# WL_RFFC.net
KiCad netlist of a schematic drawn in Altium Designer
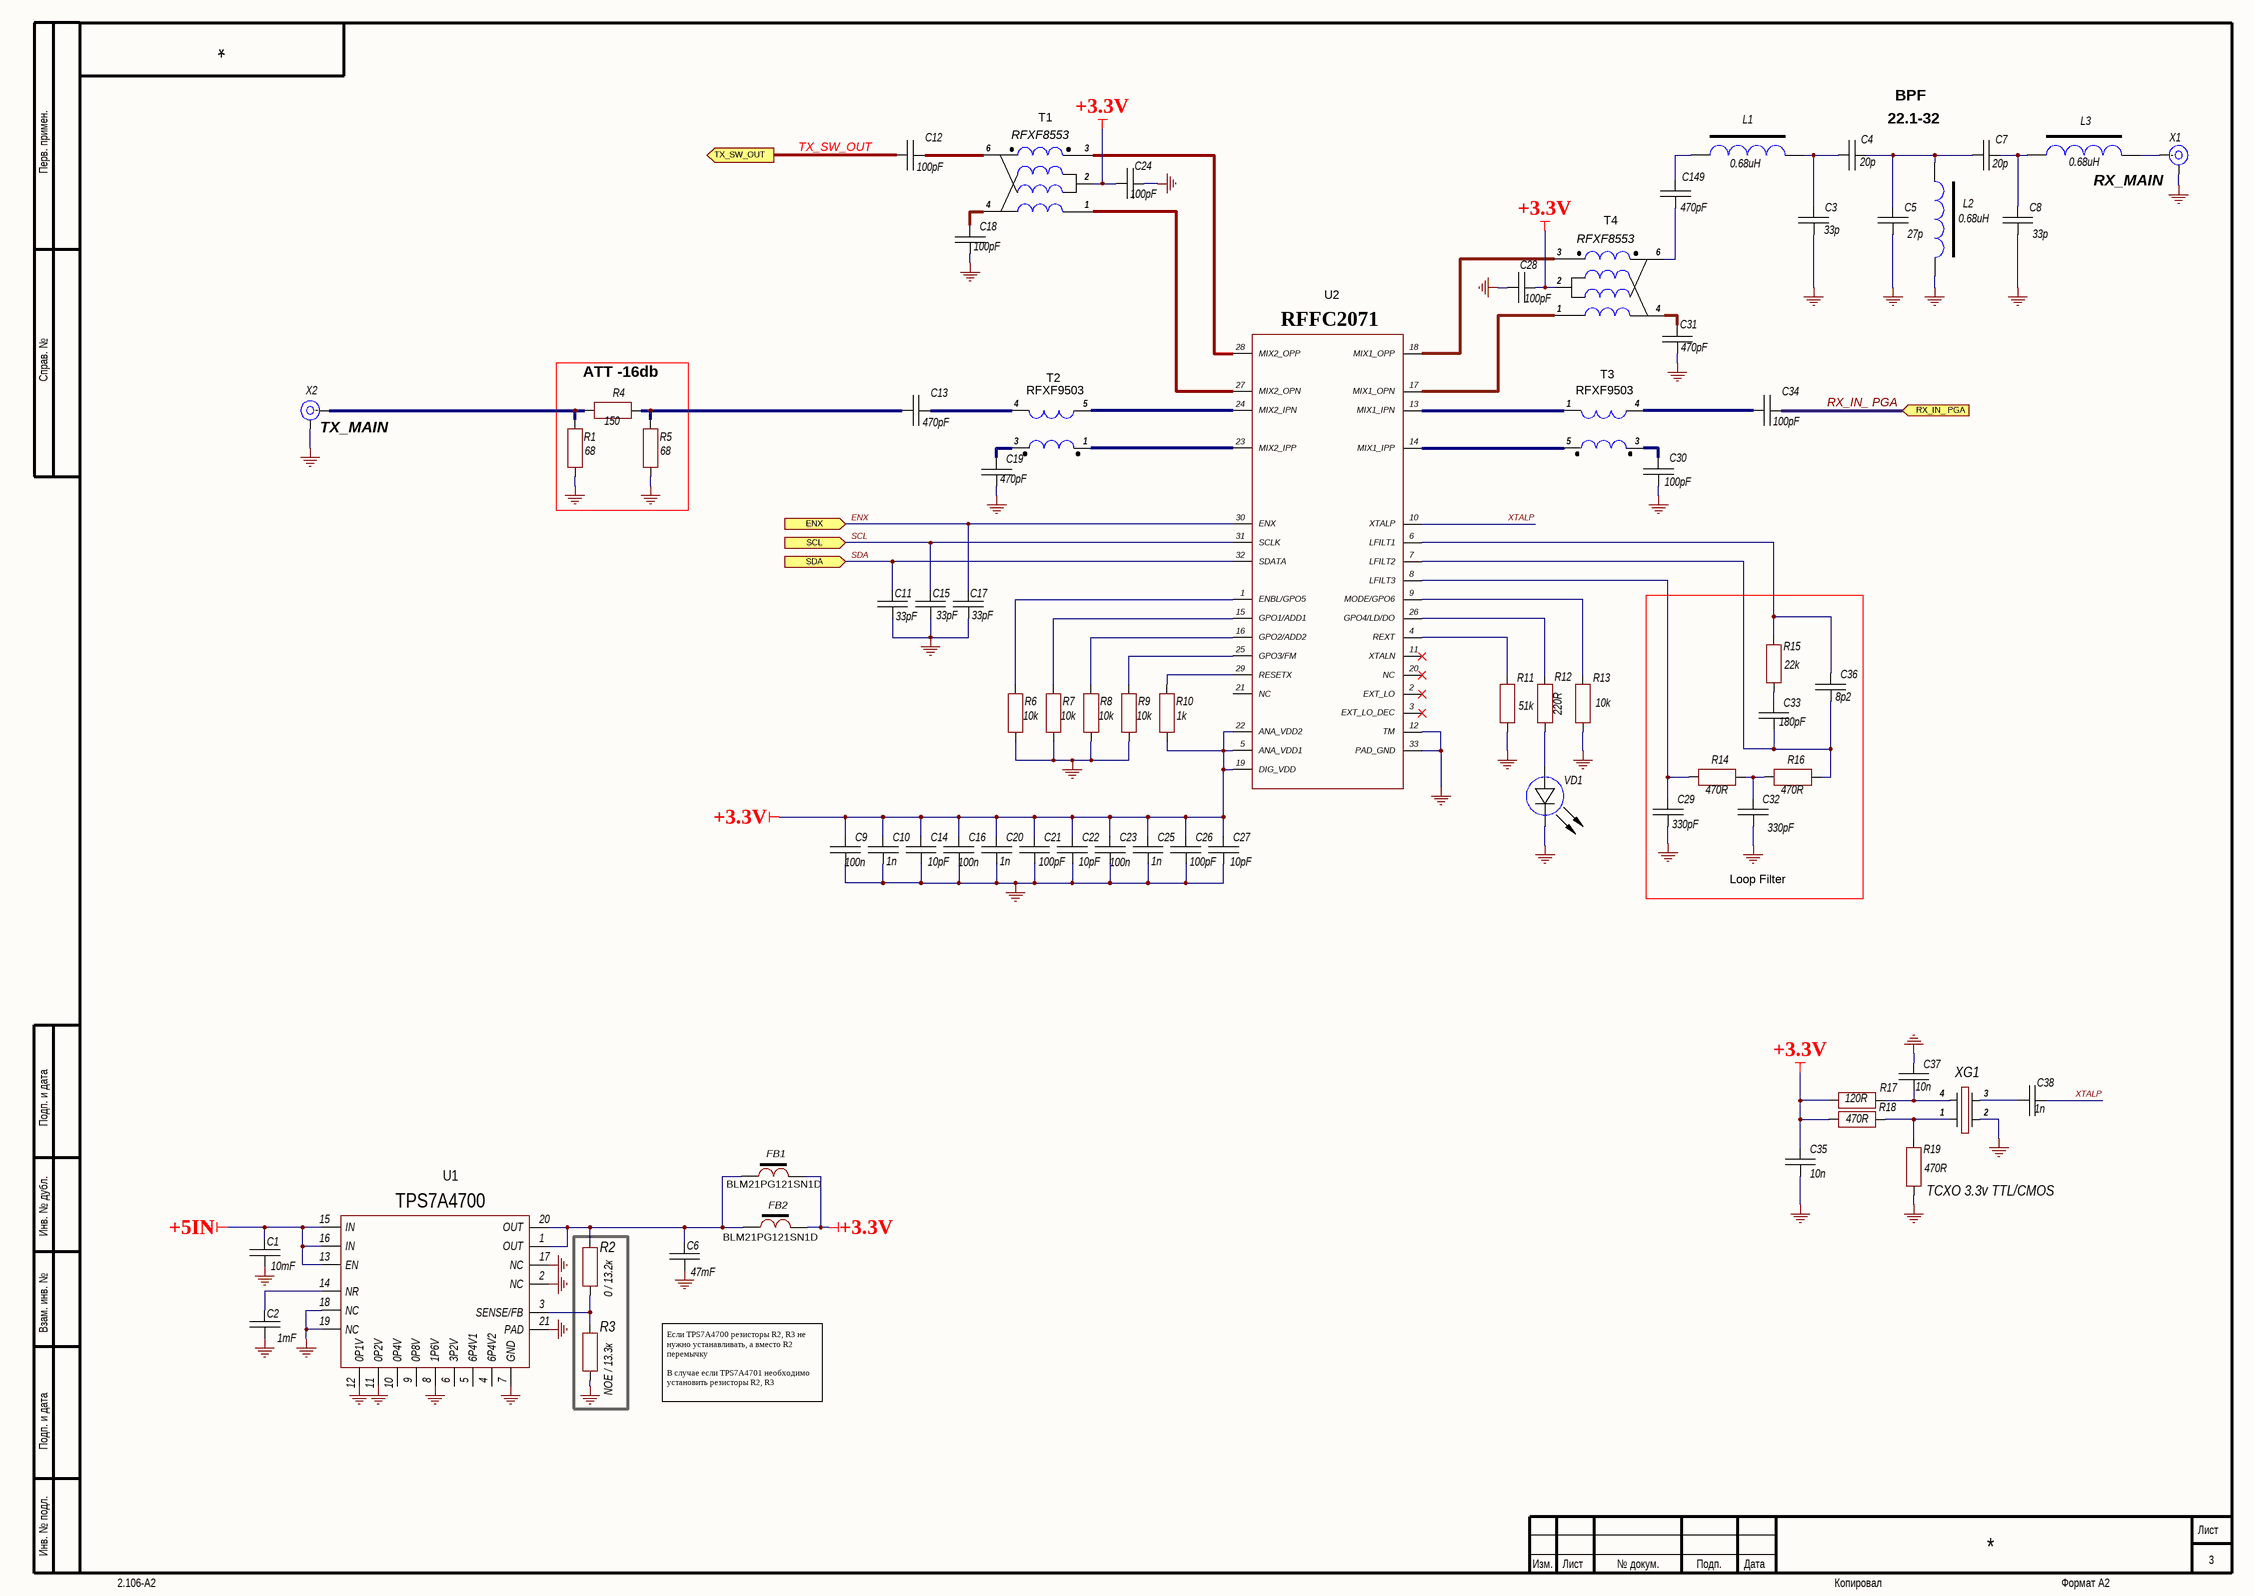
[diagram p0: WL_RFFC.SchDoc]

(export (version "E")
  (design (tool "Eeschema 10.0.6"))
  (components
    (comp (ref "C1")
      (value "10mF")
      (footprint "standard:CH1206C")
      (libsource (lib "Discrete") (part "Capacitor"))
    )
    (comp (ref "C2")
      (value "1mF")
      (footprint "standard:CH0805C")
      (libsource (lib "Discrete") (part "Capacitor"))
    )
    (comp (ref "C3")
      (value "33p")
      (footprint "standard:CH0805C")
      (libsource (lib "Discrete") (part "Capacitor"))
    )
    (comp (ref "C4")
      (value "20p")
      (footprint "standard:CH0805C")
      (libsource (lib "Discrete") (part "Capacitor"))
    )
    (comp (ref "C5")
      (value "27p")
      (footprint "standard:CH0805C")
      (libsource (lib "Discrete") (part "Capacitor"))
    )
    (comp (ref "C6")
      (value "47mF")
      (footprint "standard:CH1206C")
      (libsource (lib "Discrete") (part "Capacitor"))
    )
    (comp (ref "C7")
      (value "20p")
      (footprint "standard:CH0805C")
      (libsource (lib "Discrete") (part "Capacitor"))
    )
    (comp (ref "C8")
      (value "33p")
      (footprint "standard:CH0805C")
      (libsource (lib "Discrete") (part "Capacitor"))
    )
    (comp (ref "C9")
      (value "100n")
      (footprint "standard:CH0805C")
      (libsource (lib "Discrete") (part "Capacitor"))
    )
    (comp (ref "C10")
      (value "1n")
      (footprint "standard:CH0805C")
      (libsource (lib "Discrete") (part "Capacitor"))
    )
    (comp (ref "C11")
      (value "33pF")
      (footprint "standard:CH0805C")
      (libsource (lib "Discrete") (part "Capacitor"))
    )
    (comp (ref "C12")
      (value "100pF")
      (footprint "standard:CH0805C")
      (libsource (lib "Discrete") (part "Capacitor"))
    )
    (comp (ref "C13")
      (value "470pF")
      (footprint "standard:CH0805C")
      (libsource (lib "Discrete") (part "Capacitor"))
    )
    (comp (ref "C14")
      (value "10pF")
      (footprint "standard:CH0805C")
      (libsource (lib "Discrete") (part "Capacitor"))
    )
    (comp (ref "C15")
      (value "33pF")
      (footprint "standard:CH0805C")
      (libsource (lib "Discrete") (part "Capacitor"))
    )
    (comp (ref "C16")
      (value "100n")
      (footprint "standard:CH0805C")
      (libsource (lib "Discrete") (part "Capacitor"))
    )
    (comp (ref "C17")
      (value "33pF")
      (footprint "standard:CH0805C")
      (libsource (lib "Discrete") (part "Capacitor"))
    )
    (comp (ref "C18")
      (value "100pF")
      (footprint "standard:CH0805C")
      (libsource (lib "Discrete") (part "Capacitor"))
    )
    (comp (ref "C19")
      (value "470pF")
      (footprint "standard:CH0805C")
      (libsource (lib "Discrete") (part "Capacitor"))
    )
    (comp (ref "C20")
      (value "1n")
      (footprint "standard:CH0805C")
      (libsource (lib "Discrete") (part "Capacitor"))
    )
    (comp (ref "C21")
      (value "100pF")
      (footprint "standard:CH0805C")
      (libsource (lib "Discrete") (part "Capacitor"))
    )
    (comp (ref "C22")
      (value "10pF")
      (footprint "standard:CH0805C")
      (libsource (lib "Discrete") (part "Capacitor"))
    )
    (comp (ref "C23")
      (value "100n")
      (footprint "standard:CH0805C")
      (libsource (lib "Discrete") (part "Capacitor"))
    )
    (comp (ref "C24")
      (value "100pF")
      (footprint "standard:CH0805C")
      (libsource (lib "Discrete") (part "Capacitor"))
    )
    (comp (ref "C25")
      (value "1n")
      (footprint "standard:CH0805C")
      (libsource (lib "Discrete") (part "Capacitor"))
    )
    (comp (ref "C26")
      (value "100pF")
      (footprint "standard:CH0805C")
      (libsource (lib "Discrete") (part "Capacitor"))
    )
    (comp (ref "C27")
      (value "10pF")
      (footprint "standard:CH0805C")
      (libsource (lib "Discrete") (part "Capacitor"))
    )
    (comp (ref "C28")
      (value "100pF")
      (footprint "standard:CH0805C")
      (libsource (lib "Discrete") (part "Capacitor"))
    )
    (comp (ref "C29")
      (value "330pF")
      (footprint "standard:CH0805C")
      (libsource (lib "Discrete") (part "Capacitor"))
    )
    (comp (ref "C30")
      (value "100pF")
      (footprint "standard:CH0805C")
      (libsource (lib "Discrete") (part "Capacitor"))
    )
    (comp (ref "C31")
      (value "470pF")
      (footprint "standard:CH0805C")
      (libsource (lib "Discrete") (part "Capacitor"))
    )
    (comp (ref "C32")
      (value "330pF")
      (footprint "standard:CH0805C")
      (libsource (lib "Discrete") (part "Capacitor"))
    )
    (comp (ref "C33")
      (value "180pF")
      (footprint "standard:CH0805C")
      (libsource (lib "Discrete") (part "Capacitor"))
    )
    (comp (ref "C34")
      (value "100pF")
      (footprint "standard:CH0805C")
      (libsource (lib "Discrete") (part "Capacitor"))
    )
    (comp (ref "C35")
      (value "10n")
      (footprint "standard:CH0805C")
      (libsource (lib "Discrete") (part "Capacitor"))
    )
    (comp (ref "C36")
      (value "8p2")
      (footprint "standard:CH0805C")
      (libsource (lib "Discrete") (part "Capacitor"))
    )
    (comp (ref "C37")
      (value "10n")
      (footprint "standard:CH0805C")
      (libsource (lib "Discrete") (part "Capacitor"))
    )
    (comp (ref "C38")
      (value "1n")
      (footprint "standard:CH0805C")
      (libsource (lib "Discrete") (part "Capacitor"))
    )
    (comp (ref "C149")
      (value "470pF")
      (footprint "standard:CH0805C")
      (libsource (lib "Discrete") (part "Capacitor"))
    )
    (comp (ref "FB1")
      (value "BLM21PG121SN1D")
      (footprint "CH0805L")
      (libsource (lib "Discrete") (part "FB-1"))
    )
    (comp (ref "FB2")
      (value "BLM21PG121SN1D")
      (footprint "CH0805L")
      (libsource (lib "Discrete") (part "FB-1"))
    )
    (comp (ref "L1") (value "0.68uH") (footprint "L1210") (libsource (lib "") (part "TRANS_1")))
    (comp (ref "L2") (value "0.68uH") (footprint "L1210") (libsource (lib "Transformers") (part "TRANS")))
    (comp (ref "L3") (value "0.68uH") (footprint "L1210") (libsource (lib "") (part "TRANS_1")))
    (comp (ref "R1") (value "68") (footprint "standard:CH1206R") (libsource (lib "") (part "Resistor_1")))
    (comp (ref "R2")
      (value "0 / 13.2к")
      (footprint "standard:CH0805R")
      (libsource (lib "Discrete") (part "Resistor"))
    )
    (comp (ref "R3")
      (value "NOE / 13.3к")
      (footprint "standard:CH0805R")
      (libsource (lib "Discrete") (part "Resistor"))
    )
    (comp (ref "R4") (value "150") (footprint "standard:CH1206R") (libsource (lib "") (part "Resistor_2")))
    (comp (ref "R5") (value "68") (footprint "standard:CH1206R") (libsource (lib "") (part "Resistor_1")))
    (comp (ref "R6") (value "10k") (footprint "standard:CH0805R") (libsource (lib "") (part "Resistor_1")))
    (comp (ref "R7") (value "10k") (footprint "standard:CH0805R") (libsource (lib "") (part "Resistor_1")))
    (comp (ref "R8") (value "10k") (footprint "standard:CH0805R") (libsource (lib "") (part "Resistor_1")))
    (comp (ref "R9") (value "10k") (footprint "standard:CH0805R") (libsource (lib "") (part "Resistor_1")))
    (comp (ref "R10") (value "1k") (footprint "standard:CH0805R") (libsource (lib "") (part "Resistor_1")))
    (comp (ref "R11") (value "51k") (footprint "standard:CH0805R") (libsource (lib "") (part "Resistor_1")))
    (comp (ref "R12") (value "220R") (footprint "standard:CH0805R") (libsource (lib "") (part "Resistor_1")))
    (comp (ref "R13") (value "10k") (footprint "standard:CH0805R") (libsource (lib "") (part "Resistor_1")))
    (comp (ref "R14") (value "470R") (footprint "standard:CH0805R") (libsource (lib "") (part "Resistor_2")))
    (comp (ref "R15")
      (value "22k")
      (footprint "standard:CH0805R")
      (libsource (lib "Discrete") (part "Resistor"))
    )
    (comp (ref "R16") (value "470R") (footprint "standard:CH0805R") (libsource (lib "") (part "Resistor_2")))
    (comp (ref "R17") (value "120R") (footprint "standard:CH0805R") (libsource (lib "") (part "Resistor_2")))
    (comp (ref "R18") (value "470R") (footprint "standard:CH0805R") (libsource (lib "") (part "Resistor_2")))
    (comp (ref "R19")
      (value "470R")
      (footprint "standard:CH0805R")
      (libsource (lib "Discrete") (part "Resistor"))
    )
    (comp (ref "T1") (value "RFXF8553") (footprint "TC4-1-ADT4-6") (libsource (lib "") (part "RFXF8553_1")))
    (comp (ref "T2")
      (value "RFXF9503")
      (footprint "TC4-1/RFXF8553")
      (libsource (lib "Transformers") (part "RFXF9503"))
    )
    (comp (ref "T3") (value "RFXF9503") (footprint "TC4-1/RFXF8553") (libsource (lib "") (part "RFXF9503_1")))
    (comp (ref "T4")
      (value "RFXF8553")
      (footprint "TC4-1-ADT4-6")
      (libsource (lib "Transformers") (part "RFXF8553"))
    )
    (comp (ref "U1")
      (value "TPS7A4700")
      (footprint "20-VQFN (5x5 mm)")
      (libsource (lib "Power Supplies") (part "TPS7A4700"))
    )
    (comp (ref "U2")
      (value "RFFC2071")
      (footprint "32-VQFN (5x5 mm)")
      (libsource (lib "Digital") (part "RFFC2071"))
    )
    (comp (ref "VD1") (value "*") (footprint "standard:CH0805LB") (libsource (lib "Discrete") (part "LED")))
    (comp (ref "X1")
      (value "RX_MAIN")
      (footprint "custom:CON: SMA")
      (description "RF")
      (libsource (lib "Connectors") (part "SMA"))
    )
    (comp (ref "X2")
      (value "TX_MAIN")
      (footprint "custom:CON: SMA")
      (description "RF")
      (libsource (lib "Connectors") (part "SMA"))
    )
    (comp (ref "XG1")
      (value "TCXO 3.3v TTL/CMOS")
      (footprint "TCXO")
      (libsource (lib "Discrete") (part "Generator"))
    )
  )
  (nets
    (net (code "1") (name "+3.3V") (class "Default")
      (node (ref "C10") (pin "2") (pinfunction "2_2") (pintype "power_in"))
      (node (ref "C14") (pin "2") (pinfunction "2_2") (pintype "power_in"))
      (node (ref "C16") (pin "2") (pinfunction "2_2") (pintype "power_in"))
      (node (ref "C20") (pin "2") (pinfunction "2_2") (pintype "power_in"))
      (node (ref "C21") (pin "2") (pinfunction "2_2") (pintype "power_in"))
      (node (ref "C22") (pin "2") (pinfunction "2_2") (pintype "power_in"))
      (node (ref "C23") (pin "2") (pinfunction "2_2") (pintype "power_in"))
      (node (ref "C24") (pin "2") (pinfunction "2_2") (pintype "power_in"))
      (node (ref "C25") (pin "2") (pinfunction "2_2") (pintype "power_in"))
      (node (ref "C26") (pin "2") (pinfunction "2_2") (pintype "power_in"))
      (node (ref "C27") (pin "2") (pinfunction "2_2") (pintype "power_in"))
      (node (ref "C28") (pin "2") (pinfunction "2_2") (pintype "power_in"))
      (node (ref "C35") (pin "2") (pinfunction "2_2") (pintype "power_in"))
      (node (ref "C9") (pin "2") (pinfunction "2_2") (pintype "power_in"))
      (node (ref "FB1") (pin "2") (pinfunction "2_2") (pintype "passive"))
      (node (ref "FB2") (pin "2") (pinfunction "2_2") (pintype "passive"))
      (node (ref "R10") (pin "2") (pinfunction "2_2") (pintype "passive"))
      (node (ref "R17") (pin "1") (pinfunction "1_1") (pintype "passive"))
      (node (ref "R18") (pin "1") (pinfunction "1_1") (pintype "passive"))
      (node (ref "T1") (pin "2") (pinfunction "2_2") (pintype "passive"))
      (node (ref "T4") (pin "2") (pinfunction "2_2") (pintype "passive"))
      (node (ref "U2") (pin "19") (pinfunction "DIG_VDD_19") (pintype "passive"))
      (node (ref "U2") (pin "22") (pinfunction "ANA_VDD2_22") (pintype "passive"))
      (node (ref "U2") (pin "5") (pinfunction "ANA_VDD1_5") (pintype "passive"))
    )
    (net (code "2") (name "+5IN") (class "Default")
      (node (ref "C1") (pin "2") (pinfunction "2_2") (pintype "power_in"))
      (node (ref "U1") (pin "13") (pinfunction "EN_13") (pintype "power_in"))
      (node (ref "U1") (pin "15") (pinfunction "IN_15") (pintype "power_in"))
      (node (ref "U1") (pin "16") (pinfunction "IN_16") (pintype "power_in"))
    )
    (net (code "3") (name "/ENX") (class "Default")
      (node (ref "C17") (pin "2") (pinfunction "2_2") (pintype "power_in"))
      (node (ref "U2") (pin "30") (pinfunction "ENX_30") (pintype "passive"))
    )
    (net (code "4") (name "/RX_IN_ PGA") (class "Default")
      (node (ref "C34") (pin "1") (pinfunction "1_1") (pintype "power_in"))
    )
    (net (code "5") (name "/SCL") (class "Default")
      (node (ref "C15") (pin "2") (pinfunction "2_2") (pintype "power_in"))
      (node (ref "U2") (pin "31") (pinfunction "SCLK_31") (pintype "passive"))
    )
    (net (code "6") (name "/SDA") (class "Default")
      (node (ref "C11") (pin "2") (pinfunction "2_2") (pintype "power_in"))
      (node (ref "U2") (pin "32") (pinfunction "SDATA_32") (pintype "passive"))
    )
    (net (code "7") (name "/TX_SW_OUT") (class "Default")
      (node (ref "C12") (pin "1") (pinfunction "1_1") (pintype "power_in"))
    )
    (net (code "8") (name "/XTALP") (class "Default")
      (node (ref "C38") (pin "1") (pinfunction "1_1") (pintype "power_in"))
      (node (ref "U2") (pin "10") (pinfunction "XTALP_10") (pintype "passive"))
    )
    (net (code "9") (name "GND") (class "Default")
      (node (ref "C1") (pin "1") (pinfunction "1_1") (pintype "power_in"))
      (node (ref "C10") (pin "1") (pinfunction "1_1") (pintype "power_in"))
      (node (ref "C11") (pin "1") (pinfunction "1_1") (pintype "power_in"))
      (node (ref "C14") (pin "1") (pinfunction "1_1") (pintype "power_in"))
      (node (ref "C15") (pin "1") (pinfunction "1_1") (pintype "power_in"))
      (node (ref "C16") (pin "1") (pinfunction "1_1") (pintype "power_in"))
      (node (ref "C17") (pin "1") (pinfunction "1_1") (pintype "power_in"))
      (node (ref "C18") (pin "2") (pinfunction "2_2") (pintype "power_in"))
      (node (ref "C19") (pin "2") (pinfunction "2_2") (pintype "power_in"))
      (node (ref "C2") (pin "1") (pinfunction "1_1") (pintype "power_in"))
      (node (ref "C20") (pin "1") (pinfunction "1_1") (pintype "power_in"))
      (node (ref "C21") (pin "1") (pinfunction "1_1") (pintype "power_in"))
      (node (ref "C22") (pin "1") (pinfunction "1_1") (pintype "power_in"))
      (node (ref "C23") (pin "1") (pinfunction "1_1") (pintype "power_in"))
      (node (ref "C24") (pin "1") (pinfunction "1_1") (pintype "power_in"))
      (node (ref "C25") (pin "1") (pinfunction "1_1") (pintype "power_in"))
      (node (ref "C26") (pin "1") (pinfunction "1_1") (pintype "power_in"))
      (node (ref "C27") (pin "1") (pinfunction "1_1") (pintype "power_in"))
      (node (ref "C28") (pin "1") (pinfunction "1_1") (pintype "power_in"))
      (node (ref "C29") (pin "1") (pinfunction "1_1") (pintype "power_in"))
      (node (ref "C3") (pin "1") (pinfunction "1_1") (pintype "power_in"))
      (node (ref "C30") (pin "2") (pinfunction "2_2") (pintype "power_in"))
      (node (ref "C31") (pin "2") (pinfunction "2_2") (pintype "power_in"))
      (node (ref "C32") (pin "1") (pinfunction "1_1") (pintype "power_in"))
      (node (ref "C35") (pin "1") (pinfunction "1_1") (pintype "power_in"))
      (node (ref "C37") (pin "2") (pinfunction "2_2") (pintype "power_in"))
      (node (ref "C5") (pin "1") (pinfunction "1_1") (pintype "power_in"))
      (node (ref "C6") (pin "1") (pinfunction "1_1") (pintype "power_in"))
      (node (ref "C8") (pin "1") (pinfunction "1_1") (pintype "power_in"))
      (node (ref "C9") (pin "1") (pinfunction "1_1") (pintype "power_in"))
      (node (ref "L2") (pin "1") (pinfunction "1_1") (pintype "power_in"))
      (node (ref "R1") (pin "2") (pinfunction "2_2") (pintype "passive"))
      (node (ref "R11") (pin "2") (pinfunction "2_2") (pintype "passive"))
      (node (ref "R13") (pin "2") (pinfunction "2_2") (pintype "passive"))
      (node (ref "R19") (pin "1") (pinfunction "1_1") (pintype "passive"))
      (node (ref "R3") (pin "1") (pinfunction "1_1") (pintype "passive"))
      (node (ref "R5") (pin "2") (pinfunction "2_2") (pintype "passive"))
      (node (ref "R6") (pin "2") (pinfunction "2_2") (pintype "passive"))
      (node (ref "R7") (pin "2") (pinfunction "2_2") (pintype "passive"))
      (node (ref "R8") (pin "2") (pinfunction "2_2") (pintype "passive"))
      (node (ref "R9") (pin "2") (pinfunction "2_2") (pintype "passive"))
      (node (ref "U1") (pin "11") (pinfunction "0P2V_11") (pintype "power_in"))
      (node (ref "U1") (pin "12") (pinfunction "0P1V_12") (pintype "power_in"))
      (node (ref "U1") (pin "17") (pinfunction "NC_17") (pintype "power_in"))
      (node (ref "U1") (pin "18") (pinfunction "NC_18") (pintype "power_in"))
      (node (ref "U1") (pin "19") (pinfunction "NC_19") (pintype "power_in"))
      (node (ref "U1") (pin "2") (pinfunction "NC_2") (pintype "power_in"))
      (node (ref "U1") (pin "21") (pinfunction "PAD_21") (pintype "power_in"))
      (node (ref "U1") (pin "7") (pinfunction "GND_7") (pintype "power_in"))
      (node (ref "U1") (pin "8") (pinfunction "1P6V_8") (pintype "power_in"))
      (node (ref "U2") (pin "12") (pinfunction "TM_12") (pintype "passive"))
      (node (ref "U2") (pin "33") (pinfunction "PAD_GND_33") (pintype "passive"))
      (node (ref "VD1") (pin "2") (pinfunction "C_2") (pintype "passive"))
      (node (ref "X1") (pin "2") (pinfunction "IN_2") (pintype "passive"))
      (node (ref "X2") (pin "2") (pinfunction "IN_2") (pintype "passive"))
      (node (ref "XG1") (pin "2") (pinfunction "2_2") (pintype "passive"))
    )
    (net (code "10") (name "Net-(C3-Pad2)") (class "Default")
      (node (ref "C3") (pin "2") (pinfunction "2_2") (pintype "power_in"))
      (node (ref "C4") (pin "1") (pinfunction "1_1") (pintype "power_in"))
      (node (ref "L1") (pin "2") (pinfunction "2_2") (pintype "power_in"))
    )
    (net (code "11") (name "Net-(C4-Pad2)") (class "Default")
      (node (ref "C4") (pin "2") (pinfunction "2_2") (pintype "power_in"))
      (node (ref "C5") (pin "2") (pinfunction "2_2") (pintype "power_in"))
      (node (ref "C7") (pin "1") (pinfunction "1_1") (pintype "power_in"))
      (node (ref "L2") (pin "2") (pinfunction "2_2") (pintype "power_in"))
    )
    (net (code "12") (name "Net-(C6-Pad2)") (class "Default")
      (node (ref "C6") (pin "2") (pinfunction "2_2") (pintype "power_in"))
      (node (ref "FB1") (pin "1") (pinfunction "1_1") (pintype "passive"))
      (node (ref "FB2") (pin "1") (pinfunction "1_1") (pintype "passive"))
      (node (ref "R2") (pin "2") (pinfunction "2_2") (pintype "passive"))
      (node (ref "U1") (pin "1") (pinfunction "OUT_1") (pintype "power_in"))
      (node (ref "U1") (pin "20") (pinfunction "OUT_20") (pintype "power_in"))
    )
    (net (code "13") (name "Net-(C7-Pad2)") (class "Default")
      (node (ref "C7") (pin "2") (pinfunction "2_2") (pintype "power_in"))
      (node (ref "C8") (pin "2") (pinfunction "2_2") (pintype "power_in"))
      (node (ref "L3") (pin "1") (pinfunction "1_1") (pintype "power_in"))
    )
    (net (code "14") (name "Net-(C12-Pad2)") (class "Default")
      (node (ref "C12") (pin "2") (pinfunction "2_2") (pintype "power_in"))
      (node (ref "T1") (pin "6") (pinfunction "6_6") (pintype "passive"))
    )
    (net (code "15") (name "Net-(C13-Pad1)") (class "Default")
      (node (ref "C13") (pin "1") (pinfunction "1_1") (pintype "power_in"))
      (node (ref "R4") (pin "2") (pinfunction "2_2") (pintype "passive"))
      (node (ref "R5") (pin "1") (pinfunction "1_1") (pintype "passive"))
    )
    (net (code "16") (name "Net-(C13-Pad2)") (class "Default")
      (node (ref "C13") (pin "2") (pinfunction "2_2") (pintype "power_in"))
      (node (ref "T2") (pin "4") (pinfunction "4_4") (pintype "passive"))
    )
    (net (code "17") (name "Net-(C18-Pad1)") (class "Default")
      (node (ref "C18") (pin "1") (pinfunction "1_1") (pintype "power_in"))
      (node (ref "T1") (pin "4") (pinfunction "4_4") (pintype "passive"))
    )
    (net (code "18") (name "Net-(C19-Pad1)") (class "Default")
      (node (ref "C19") (pin "1") (pinfunction "1_1") (pintype "power_in"))
      (node (ref "T2") (pin "3") (pinfunction "3_3") (pintype "passive"))
    )
    (net (code "19") (name "Net-(C30-Pad1)") (class "Default")
      (node (ref "C30") (pin "1") (pinfunction "1_1") (pintype "power_in"))
      (node (ref "T3") (pin "3") (pinfunction "3_3") (pintype "passive"))
    )
    (net (code "20") (name "Net-(C31-Pad1)") (class "Default")
      (node (ref "C31") (pin "1") (pinfunction "1_1") (pintype "power_in"))
      (node (ref "T4") (pin "4") (pinfunction "4_4") (pintype "passive"))
    )
    (net (code "21") (name "Net-(C32-Pad2)") (class "Default")
      (node (ref "C32") (pin "2") (pinfunction "2_2") (pintype "power_in"))
      (node (ref "R14") (pin "2") (pinfunction "2_2") (pintype "passive"))
      (node (ref "R16") (pin "1") (pinfunction "1_1") (pintype "passive"))
    )
    (net (code "22") (name "Net-(C33-Pad2)") (class "Default")
      (node (ref "C33") (pin "2") (pinfunction "2_2") (pintype "power_in"))
      (node (ref "R15") (pin "1") (pinfunction "1_1") (pintype "passive"))
    )
    (net (code "23") (name "Net-(C34-Pad2)") (class "Default")
      (node (ref "C34") (pin "2") (pinfunction "2_2") (pintype "power_in"))
      (node (ref "T3") (pin "4") (pinfunction "4_4") (pintype "passive"))
    )
    (net (code "24") (name "Net-(C37-Pad1)") (class "Default")
      (node (ref "C37") (pin "1") (pinfunction "1_1") (pintype "power_in"))
      (node (ref "R17") (pin "2") (pinfunction "2_2") (pintype "passive"))
      (node (ref "XG1") (pin "4") (pinfunction "4_4") (pintype "passive"))
    )
    (net (code "25") (name "Net-(C38-Pad2)") (class "Default")
      (node (ref "C38") (pin "2") (pinfunction "2_2") (pintype "power_in"))
      (node (ref "XG1") (pin "3") (pinfunction "3_3") (pintype "passive"))
    )
    (net (code "26") (name "Net-(C149-Pad1)") (class "Default")
      (node (ref "C149") (pin "1") (pinfunction "1_1") (pintype "power_in"))
      (node (ref "L1") (pin "1") (pinfunction "1_1") (pintype "power_in"))
    )
    (net (code "27") (name "Net-(C149-Pad2)") (class "Default")
      (node (ref "C149") (pin "2") (pinfunction "2_2") (pintype "power_in"))
      (node (ref "T4") (pin "6") (pinfunction "6_6") (pintype "passive"))
    )
    (net (code "28") (name "Net-(L3-Pad2)") (class "Default")
      (node (ref "L3") (pin "2") (pinfunction "2_2") (pintype "power_in"))
      (node (ref "X1") (pin "1") (pinfunction "IN_1") (pintype "passive"))
    )
    (net (code "29") (name "Net-(R1-Pad1)") (class "Default")
      (node (ref "R1") (pin "1") (pinfunction "1_1") (pintype "passive"))
      (node (ref "R4") (pin "1") (pinfunction "1_1") (pintype "passive"))
      (node (ref "X2") (pin "1") (pinfunction "IN_1") (pintype "passive"))
    )
    (net (code "30") (name "Net-(R18-Pad2)") (class "Default")
      (node (ref "R18") (pin "2") (pinfunction "2_2") (pintype "passive"))
      (node (ref "R19") (pin "2") (pinfunction "2_2") (pintype "passive"))
      (node (ref "XG1") (pin "1") (pinfunction "1_1") (pintype "passive"))
    )
    (net (code "31") (name "Net-(U1-NR)") (class "Default")
      (node (ref "C2") (pin "2") (pinfunction "2_2") (pintype "power_in"))
      (node (ref "U1") (pin "14") (pinfunction "NR_14") (pintype "power_in"))
    )
    (net (code "32") (name "Net-(U1-SENSE{slash}FB)") (class "Default")
      (node (ref "R2") (pin "1") (pinfunction "1_1") (pintype "passive"))
      (node (ref "R3") (pin "2") (pinfunction "2_2") (pintype "passive"))
      (node (ref "U1") (pin "3") (pinfunction "SENSE/FB_3") (pintype "power_in"))
    )
    (net (code "33") (name "Net-(U2-ENBL{slash}GPO5)") (class "Default")
      (node (ref "R6") (pin "1") (pinfunction "1_1") (pintype "passive"))
      (node (ref "U2") (pin "1") (pinfunction "ENBL/GPO5_1") (pintype "passive"))
    )
    (net (code "34") (name "Net-(U2-GPO1{slash}ADD1)") (class "Default")
      (node (ref "R7") (pin "1") (pinfunction "1_1") (pintype "passive"))
      (node (ref "U2") (pin "15") (pinfunction "GPO1/ADD1_15") (pintype "passive"))
    )
    (net (code "35") (name "Net-(U2-GPO2{slash}ADD2)") (class "Default")
      (node (ref "R8") (pin "1") (pinfunction "1_1") (pintype "passive"))
      (node (ref "U2") (pin "16") (pinfunction "GPO2/ADD2_16") (pintype "passive"))
    )
    (net (code "36") (name "Net-(U2-GPO3{slash}FM)") (class "Default")
      (node (ref "R9") (pin "1") (pinfunction "1_1") (pintype "passive"))
      (node (ref "U2") (pin "25") (pinfunction "GPO3/FM_25") (pintype "passive"))
    )
    (net (code "37") (name "Net-(U2-GPO4{slash}LD{slash}DO)") (class "Default")
      (node (ref "R12") (pin "1") (pinfunction "1_1") (pintype "passive"))
      (node (ref "U2") (pin "26") (pinfunction "GPO4/LD/DO_26") (pintype "passive"))
    )
    (net (code "38") (name "Net-(U2-LFILT1)") (class "Default")
      (node (ref "C36") (pin "2") (pinfunction "2_2") (pintype "power_in"))
      (node (ref "R15") (pin "2") (pinfunction "2_2") (pintype "passive"))
      (node (ref "U2") (pin "6") (pinfunction "LFILT1_6") (pintype "passive"))
    )
    (net (code "39") (name "Net-(U2-LFILT2)") (class "Default")
      (node (ref "C33") (pin "1") (pinfunction "1_1") (pintype "power_in"))
      (node (ref "C36") (pin "1") (pinfunction "1_1") (pintype "power_in"))
      (node (ref "R16") (pin "2") (pinfunction "2_2") (pintype "passive"))
      (node (ref "U2") (pin "7") (pinfunction "LFILT2_7") (pintype "passive"))
    )
    (net (code "40") (name "Net-(U2-LFILT3)") (class "Default")
      (node (ref "C29") (pin "2") (pinfunction "2_2") (pintype "power_in"))
      (node (ref "R14") (pin "1") (pinfunction "1_1") (pintype "passive"))
      (node (ref "U2") (pin "8") (pinfunction "LFILT3_8") (pintype "passive"))
    )
    (net (code "41") (name "Net-(U2-MIX1_IPN)") (class "Default")
      (node (ref "T3") (pin "1") (pinfunction "1_1") (pintype "passive"))
      (node (ref "U2") (pin "13") (pinfunction "MIX1_IPN_13") (pintype "passive"))
    )
    (net (code "42") (name "Net-(U2-MIX1_IPP)") (class "Default")
      (node (ref "T3") (pin "5") (pinfunction "5_5") (pintype "passive"))
      (node (ref "U2") (pin "14") (pinfunction "MIX1_IPP_14") (pintype "passive"))
    )
    (net (code "43") (name "Net-(U2-MIX1_OPN)") (class "Default")
      (node (ref "T4") (pin "1") (pinfunction "1_1") (pintype "passive"))
      (node (ref "U2") (pin "17") (pinfunction "MIX1_OPN_17") (pintype "passive"))
    )
    (net (code "44") (name "Net-(U2-MIX1_OPP)") (class "Default")
      (node (ref "T4") (pin "3") (pinfunction "3_3") (pintype "passive"))
      (node (ref "U2") (pin "18") (pinfunction "MIX1_OPP_18") (pintype "passive"))
    )
    (net (code "45") (name "Net-(U2-MIX2_IPN)") (class "Default")
      (node (ref "T2") (pin "5") (pinfunction "5_5") (pintype "passive"))
      (node (ref "U2") (pin "24") (pinfunction "MIX2_IPN_24") (pintype "passive"))
    )
    (net (code "46") (name "Net-(U2-MIX2_IPP)") (class "Default")
      (node (ref "T2") (pin "1") (pinfunction "1_1") (pintype "passive"))
      (node (ref "U2") (pin "23") (pinfunction "MIX2_IPP_23") (pintype "passive"))
    )
    (net (code "47") (name "Net-(U2-MIX2_OPN)") (class "Default")
      (node (ref "T1") (pin "1") (pinfunction "1_1") (pintype "passive"))
      (node (ref "U2") (pin "27") (pinfunction "MIX2_OPN_27") (pintype "passive"))
    )
    (net (code "48") (name "Net-(U2-MIX2_OPP)") (class "Default")
      (node (ref "T1") (pin "3") (pinfunction "3_3") (pintype "passive"))
      (node (ref "U2") (pin "28") (pinfunction "MIX2_OPP_28") (pintype "passive"))
    )
    (net (code "49") (name "Net-(U2-MODE{slash}GPO6)") (class "Default")
      (node (ref "R13") (pin "1") (pinfunction "1_1") (pintype "passive"))
      (node (ref "U2") (pin "9") (pinfunction "MODE/GPO6_9") (pintype "passive"))
    )
    (net (code "50") (name "Net-(U2-RESETX)") (class "Default")
      (node (ref "R10") (pin "1") (pinfunction "1_1") (pintype "passive"))
      (node (ref "U2") (pin "29") (pinfunction "RESETX_29") (pintype "passive"))
    )
    (net (code "51") (name "Net-(U2-REXT)") (class "Default")
      (node (ref "R11") (pin "1") (pinfunction "1_1") (pintype "passive"))
      (node (ref "U2") (pin "4") (pinfunction "REXT_4") (pintype "passive"))
    )
    (net (code "52") (name "Net-(VD1-A)") (class "Default")
      (node (ref "R12") (pin "2") (pinfunction "2_2") (pintype "passive"))
      (node (ref "VD1") (pin "1") (pinfunction "A_1") (pintype "passive"))
    )
    (net (code "53") (name "unconnected-(U1-0P4V-Pad10)") (class "Default")
      (node (ref "U1") (pin "10") (pinfunction "0P4V_10") (pintype "power_in"))
    )
    (net (code "54") (name "unconnected-(U1-0P8V-Pad9)") (class "Default")
      (node (ref "U1") (pin "9") (pinfunction "0P8V_9") (pintype "power_in"))
    )
    (net (code "55") (name "unconnected-(U1-3P2V-Pad6)") (class "Default")
      (node (ref "U1") (pin "6") (pinfunction "3P2V_6") (pintype "power_in"))
    )
    (net (code "56") (name "unconnected-(U1-6P4V1-Pad5)") (class "Default")
      (node (ref "U1") (pin "5") (pinfunction "6P4V1_5") (pintype "power_in"))
    )
    (net (code "57") (name "unconnected-(U1-6P4V2-Pad4)") (class "Default")
      (node (ref "U1") (pin "4") (pinfunction "6P4V2_4") (pintype "power_in"))
    )
    (net (code "58") (name "unconnected-(U2-EXT_LO-Pad2)") (class "Default")
      (node (ref "U2") (pin "2") (pinfunction "EXT_LO_2") (pintype "passive+no_connect"))
    )
    (net (code "59") (name "unconnected-(U2-EXT_LO_DEC-Pad3)") (class "Default")
      (node (ref "U2") (pin "3") (pinfunction "EXT_LO_DEC_3") (pintype "passive+no_connect"))
    )
    (net (code "60") (name "unconnected-(U2-NC-Pad20)") (class "Default")
      (node (ref "U2") (pin "20") (pinfunction "NC_20") (pintype "passive+no_connect"))
    )
    (net (code "61") (name "unconnected-(U2-NC-Pad21)") (class "Default")
      (node (ref "U2") (pin "21") (pinfunction "NC_21") (pintype "passive"))
    )
    (net (code "62") (name "unconnected-(U2-XTALN-Pad11)") (class "Default")
      (node (ref "U2") (pin "11") (pinfunction "XTALN_11") (pintype "passive+no_connect"))
    )
  )
)
